# BEP31_RPM_BAR_switchedRES_2.net
KiCad netlist of a schematic drawn in EAGLE
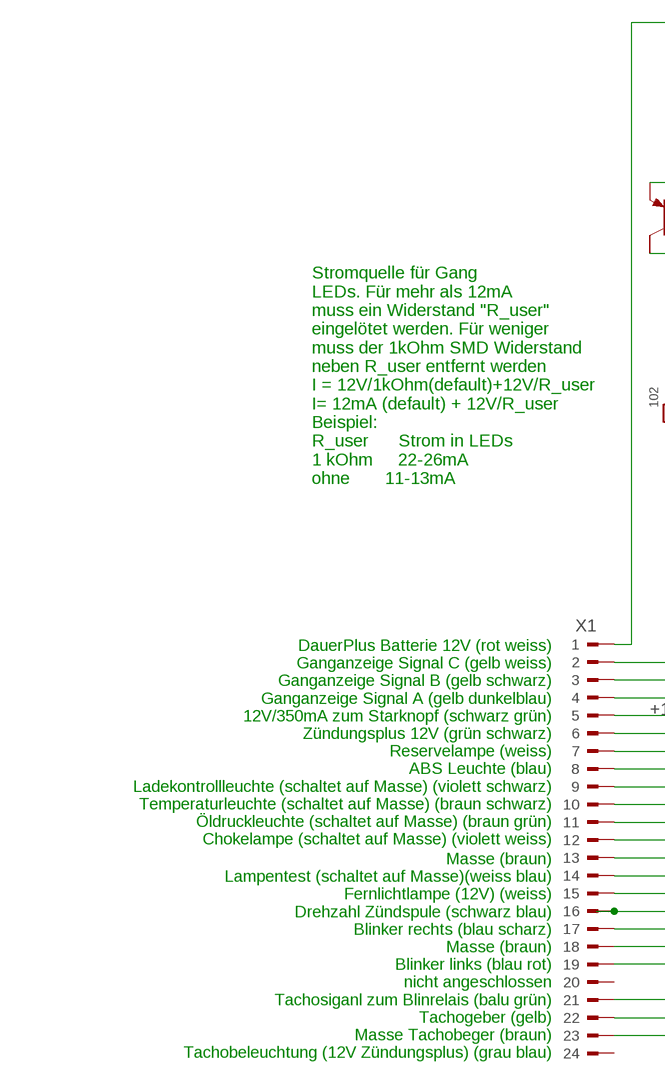
[diagram p0: schematic, sheet 1, part 1 of 2]
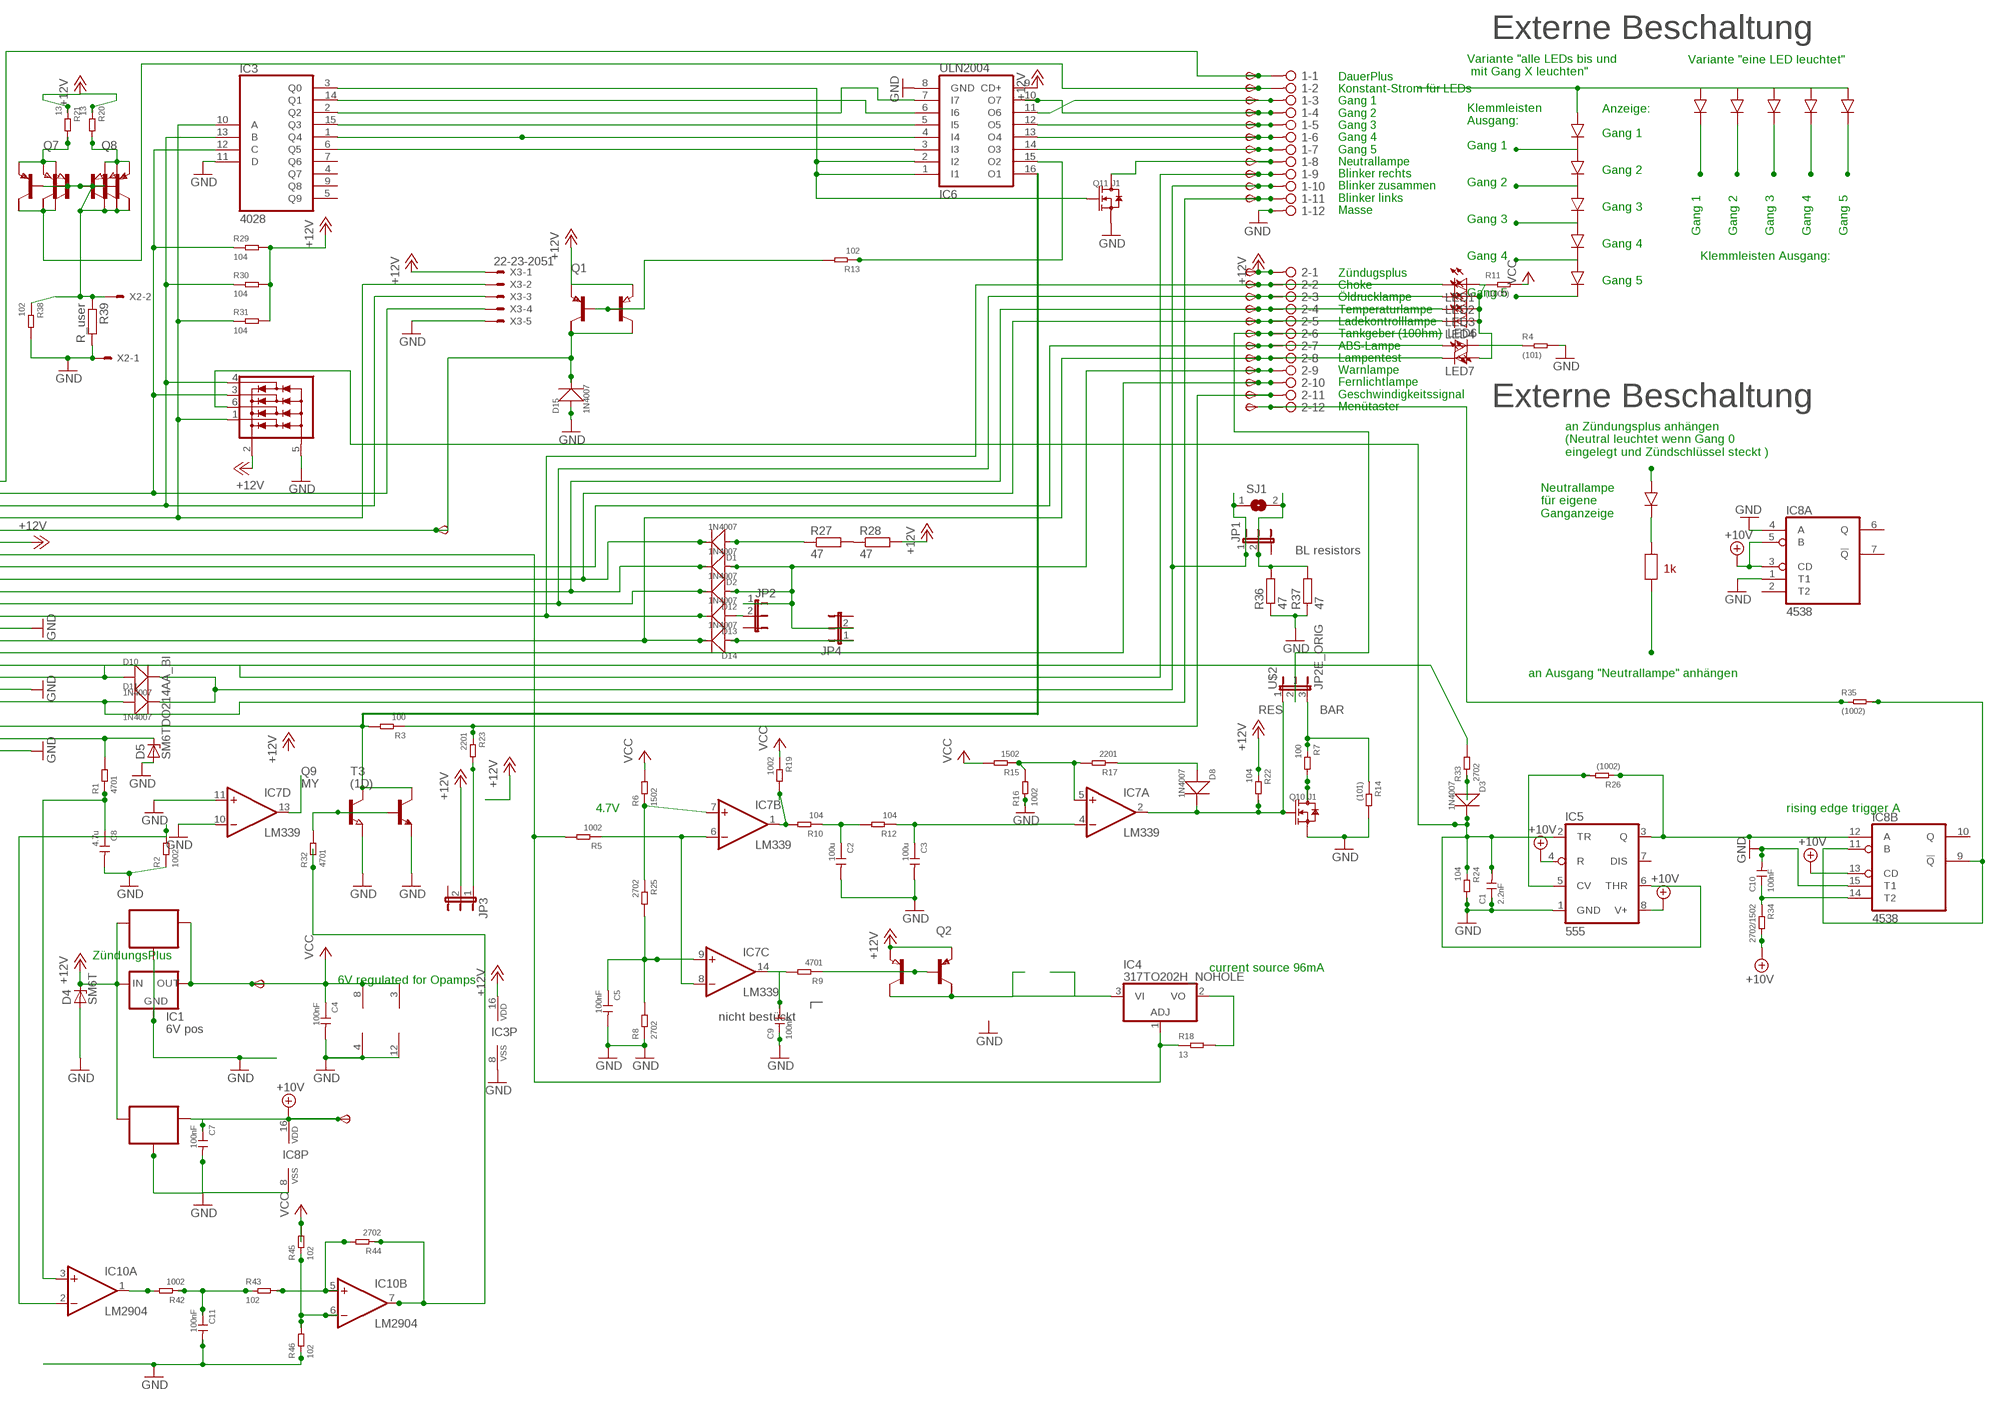
[diagram p1: schematic, sheet 1, part 2 of 2]

(export (version "E")
  (design (tool "Eeschema 10.0.6"))
  (components
    (comp (ref "1")
      (value "2081-1132")
      (footprint "eagle-import:12-PIN")
      (libsource (lib "eagle-import") (part "2081-1132"))
    )
    (comp (ref "2")
      (value "2081-1132")
      (footprint "eagle-import:12-PIN")
      (libsource (lib "eagle-import") (part "2081-1132"))
    )
    (comp (ref "6V")
      (value "TPSB2.0")
      (footprint "eagle-import:B2.0")
      (libsource (lib "eagle-import") (part "TPSB2.0"))
    )
    (comp (ref "10V")
      (value "TPSB2.0")
      (footprint "eagle-import:B2.0")
      (libsource (lib "eagle-import") (part "TPSB2.0"))
    )
    (comp (ref "C1")
      (value "2.2nF")
      (footprint "eagle-import:C0805")
      (fields (field (name "MPN") "CC0805KRX7R9BB104"))
      (libsource (lib "eagle-import") (part "CERAMIC-100NF-50V-10%-X7R(0805)"))
    )
    (comp (ref "C2")
      (value "100u")
      (footprint "eagle-import:C1206")
      (fields (field (name "MPN") "GRM31CR60J107ME39L"))
      (libsource (lib "eagle-import") (part "CERAMIC-100UF-6.3V-20%-X5R(1206)"))
    )
    (comp (ref "C3")
      (value "100u")
      (footprint "eagle-import:C1206")
      (fields (field (name "MPN") "GRM31CR60J107ME39L"))
      (libsource (lib "eagle-import") (part "CERAMIC-100UF-6.3V-20%-X5R(1206)"))
    )
    (comp (ref "C4")
      (value "100nF")
      (footprint "eagle-import:C0805")
      (fields (field (name "MPN") "CC0805KRX7R9BB104"))
      (libsource (lib "eagle-import") (part "CERAMIC-100NF-50V-10%-X7R(0805)"))
    )
    (comp (ref "C5")
      (value "100nF")
      (footprint "eagle-import:C0805")
      (fields (field (name "MPN") "CC0805KRX7R9BB104"))
      (libsource (lib "eagle-import") (part "CERAMIC-100NF-50V-10%-X7R(0805)"))
    )
    (comp (ref "C7")
      (value "100nF")
      (footprint "eagle-import:C0805")
      (fields (field (name "MPN") "CC0805KRX7R9BB104"))
      (libsource (lib "eagle-import") (part "CERAMIC-100NF-50V-10%-X7R(0805)"))
    )
    (comp (ref "C8")
      (value "4.7u")
      (footprint "eagle-import:C0805")
      (fields (field (name "MPN") "CC0805KKX5R8BB475"))
      (libsource (lib "eagle-import") (part "CERAMIC-4.7UF-25V-10%-X5R(0805)"))
    )
    (comp (ref "C9")
      (value "100nF")
      (footprint "eagle-import:C0805")
      (fields (field (name "MPN") "CC0805KRX7R9BB104"))
      (libsource (lib "eagle-import") (part "CERAMIC-100NF-50V-10%-X7R(0805)"))
    )
    (comp (ref "C10")
      (value "100nF")
      (footprint "eagle-import:C0805")
      (fields (field (name "MPN") "CC0805KRX7R9BB104"))
      (libsource (lib "eagle-import") (part "CERAMIC-100NF-50V-10%-X7R(0805)"))
    )
    (comp (ref "C11")
      (value "100nF")
      (footprint "eagle-import:C0805")
      (fields (field (name "MPN") "CC0805KRX7R9BB104"))
      (libsource (lib "eagle-import") (part "CERAMIC-100NF-50V-10%-X7R(0805)"))
    )
    (comp (ref "D1")
      (value "1N4007")
      (footprint "eagle-import:DO-214AC")
      (libsource (lib "eagle-import") (part "DIODE-GEN-PURPOSE-1KV-1A(DO-214AC)"))
    )
    (comp (ref "D2")
      (value "1N4007")
      (footprint "eagle-import:DO-214AC-1206MOUNT")
      (libsource (lib "eagle-import") (part "DIODE-GEN-PURPOSE-1KV-1A(DO-214AC)DO-214AC/1206"))
    )
    (comp (ref "D3")
      (value "1N4007")
      (footprint "eagle-import:DO-214AC")
      (libsource (lib "eagle-import") (part "DIODE-GEN-PURPOSE-1KV-1A(DO-214AC)"))
    )
    (comp (ref "D4")
      (value "SM6T")
      (footprint "eagle-import:DO214AA")
      (libsource (lib "eagle-import") (part "SM6T"))
    )
    (comp (ref "D5")
      (value "SM6TDO214AA_BI")
      (footprint "eagle-import:DO214AA_BI")
      (libsource (lib "eagle-import") (part "SM6TDO214AA_BI"))
    )
    (comp (ref "D8")
      (value "1N4007")
      (footprint "eagle-import:DO-214AC")
      (libsource (lib "eagle-import") (part "DIODE-GEN-PURPOSE-1KV-1A(DO-214AC)"))
    )
    (comp (ref "D10")
      (value "1N4007")
      (footprint "eagle-import:DO-214AC")
      (libsource (lib "eagle-import") (part "DIODE-GEN-PURPOSE-1KV-1A(DO-214AC)"))
    )
    (comp (ref "D11")
      (value "1N4007")
      (footprint "eagle-import:DO-214AC")
      (libsource (lib "eagle-import") (part "DIODE-GEN-PURPOSE-1KV-1A(DO-214AC)"))
    )
    (comp (ref "D12")
      (value "1N4007")
      (footprint "eagle-import:DO-214AC-1206MOUNT")
      (libsource (lib "eagle-import") (part "DIODE-GEN-PURPOSE-1KV-1A(DO-214AC)DO-214AC/1206"))
    )
    (comp (ref "D13")
      (value "1N4007")
      (footprint "eagle-import:DO-214AC-1206MOUNT")
      (libsource (lib "eagle-import") (part "DIODE-GEN-PURPOSE-1KV-1A(DO-214AC)DO-214AC/1206"))
    )
    (comp (ref "D14")
      (value "1N4007")
      (footprint "eagle-import:DO-214AC-1206MOUNT")
      (libsource (lib "eagle-import") (part "DIODE-GEN-PURPOSE-1KV-1A(DO-214AC)DO-214AC/1206"))
    )
    (comp (ref "D15")
      (value "1N4007")
      (footprint "eagle-import:DO-214AC")
      (libsource (lib "eagle-import") (part "DIODE-GEN-PURPOSE-1KV-1A(DO-214AC)"))
    )
    (comp (ref "IC1")
      (value "6V pos")
      (footprint "eagle-import:78LXX")
      (libsource (lib "eagle-import") (part "v-reg_78LXX"))
    )
    (comp (ref "IC2")
      (value "78LXXSOT89_ROUND")
      (footprint "eagle-import:SOT89_ROUND")
      (libsource (lib "eagle-import") (part "78LXXSOT89_ROUND"))
    )
    (comp (ref "IC3")
      (value "4028")
      (footprint "eagle-import:SO16")
      (libsource (lib "eagle-import") (part "4028D"))
    )
    (comp (ref "IC4")
      (value "317TO202H_NOHOLE")
      (footprint "eagle-import:TO220H_NOHOLE")
      (libsource (lib "eagle-import") (part "317TO202H_NOHOLE"))
    )
    (comp (ref "IC5")
      (value "555")
      (footprint "eagle-import:SO08")
      (libsource (lib "eagle-import") (part "555DNE"))
    )
    (comp (ref "IC6")
      (value "ULN2004")
      (footprint "eagle-import:SO16")
      (libsource (lib "eagle-import") (part "ULN2004AD"))
    )
    (comp (ref "IC7")
      (value "LM339")
      (footprint "eagle-import:SO14")
      (libsource (lib "eagle-import") (part "LM339D"))
    )
    (comp (ref "IC8")
      (value "4538")
      (footprint "eagle-import:SO16")
      (libsource (lib "eagle-import") (part "4538D"))
    )
    (comp (ref "IC9")
      (value "78LXXSOT89_ROUND")
      (footprint "eagle-import:SOT89_ROUND")
      (libsource (lib "eagle-import") (part "78LXXSOT89_ROUND"))
    )
    (comp (ref "IC10")
      (value "LM2904")
      (footprint "eagle-import:SO08")
      (libsource (lib "eagle-import") (part "LM358D"))
    )
    (comp (ref "JP1")
      (value "JP2EJP2_SMALLPADS")
      (footprint "eagle-import:JP2_SMALLPADS")
      (libsource (lib "eagle-import") (part "JP2EJP2_SMALLPADS"))
    )
    (comp (ref "JP2")
      (value "JP2EJP2_SMALLPADS")
      (footprint "eagle-import:JP2_SMALLPADS")
      (libsource (lib "eagle-import") (part "JP2EJP2_SMALLPADS"))
    )
    (comp (ref "JP3")
      (value "JP2EJP2_SMALLPADS")
      (footprint "eagle-import:JP2_SMALLPADS")
      (libsource (lib "eagle-import") (part "JP2EJP2_SMALLPADS"))
    )
    (comp (ref "JP4")
      (value "JP2EJP2_SMALLPADS")
      (footprint "eagle-import:JP2_SMALLPADS")
      (libsource (lib "eagle-import") (part "JP2EJP2_SMALLPADS"))
    )
    (comp (ref "LED1")
      (value "LEDLD260")
      (footprint "eagle-import:LD260")
      (libsource (lib "eagle-import") (part "LEDLD260"))
    )
    (comp (ref "LED2")
      (value "LEDLD260")
      (footprint "eagle-import:LD260")
      (libsource (lib "eagle-import") (part "LEDLD260"))
    )
    (comp (ref "LED3")
      (value "LEDLD260")
      (footprint "eagle-import:LD260")
      (libsource (lib "eagle-import") (part "LEDLD260"))
    )
    (comp (ref "LED4")
      (value "LEDLD260")
      (footprint "eagle-import:LD260")
      (libsource (lib "eagle-import") (part "LEDLD260"))
    )
    (comp (ref "LED6")
      (value "LEDLD260")
      (footprint "eagle-import:LD260")
      (libsource (lib "eagle-import") (part "LEDLD260"))
    )
    (comp (ref "LED7")
      (value "LEDLD260")
      (footprint "eagle-import:LD260")
      (libsource (lib "eagle-import") (part "LEDLD260"))
    )
    (comp (ref "Q1")
      (value "PNP-TRANSISTOR_SOT89")
      (footprint "eagle-import:SOT89")
      (libsource (lib "eagle-import") (part "PNP-TRANSISTOR_SOT89"))
    )
    (comp (ref "Q2")
      (value "PNP-TRANSISTOR_SOT89")
      (footprint "eagle-import:SOT89")
      (libsource (lib "eagle-import") (part "PNP-TRANSISTOR_SOT89"))
    )
    (comp (ref "Q3")
      (value "AH-16")
      (footprint "eagle-import:SOT223")
      (libsource (lib "eagle-import") (part "BCP53T1"))
    )
    (comp (ref "Q4")
      (value "(AH-16)")
      (footprint "eagle-import:SOT223")
      (libsource (lib "eagle-import") (part "BCP53T1"))
    )
    (comp (ref "Q5")
      (value "(AH-16)")
      (footprint "eagle-import:SOT223")
      (libsource (lib "eagle-import") (part "BCP53T1"))
    )
    (comp (ref "Q6")
      (value "(AH-16)")
      (footprint "eagle-import:SOT223")
      (libsource (lib "eagle-import") (part "BCP53T1"))
    )
    (comp (ref "Q7")
      (value "PNP-TRANSISTOR_SOT89")
      (footprint "eagle-import:SOT89")
      (libsource (lib "eagle-import") (part "PNP-TRANSISTOR_SOT89"))
    )
    (comp (ref "Q8")
      (value "PNP-TRANSISTOR_SOT89")
      (footprint "eagle-import:SOT89")
      (libsource (lib "eagle-import") (part "PNP-TRANSISTOR_SOT89"))
    )
    (comp (ref "Q9")
      (value "MY")
      (footprint "eagle-import:SOT89")
      (libsource (lib "eagle-import") (part "NPN-TRANSISTOR_SOT89"))
    )
    (comp (ref "Q10")
      (value "J1")
      (footprint "eagle-import:SOT-23")
      (fields (field (name "MPN") "BSS138W-7-F"))
      (libsource (lib "eagle-import") (part "SMD-MOSFET-N-CH-50V-200MA-BSS138W-7-F(SOT-23)"))
    )
    (comp (ref "Q11")
      (value "J1")
      (footprint "eagle-import:SOT-23")
      (fields (field (name "MPN") "BSS138W-7-F"))
      (libsource (lib "eagle-import") (part "SMD-MOSFET-N-CH-50V-200MA-BSS138W-7-F(SOT-23)"))
    )
    (comp (ref "R1")
      (value "4701")
      (footprint "eagle-import:R0805")
      (fields (field (name "MPN") "RC0805JR-074K7L"))
      (libsource (lib "eagle-import") (part "SMD-RES-4.7K-5%-1/8W(0805)"))
    )
    (comp (ref "R2")
      (value "1002")
      (footprint "eagle-import:R0805")
      (fields (field (name "MPN") "RC0805FR-0710KL"))
      (libsource (lib "eagle-import") (part "SMD-RES-10K-1%-1/8W(0805)"))
    )
    (comp (ref "R3")
      (value "100")
      (footprint "eagle-import:R0805")
      (fields (field (name "MPN") "RC0805JR-07220RL"))
      (libsource (lib "eagle-import") (part "SMD-RES-220R-5%-1/8W(0805)"))
    )
    (comp (ref "R4")
      (value "(101)")
      (footprint "eagle-import:R0805")
      (fields (field (name "MPN") "RC0805JR-07100RL"))
      (libsource (lib "eagle-import") (part "SMD-RES-100R-5%-1/8W(0805)"))
    )
    (comp (ref "R5")
      (value "1002")
      (footprint "eagle-import:R0805")
      (fields (field (name "MPN") "RC0805FR-0710KL"))
      (libsource (lib "eagle-import") (part "SMD-RES-10K-1%-1/8W(0805)"))
    )
    (comp (ref "R6")
      (value "1502")
      (footprint "eagle-import:R0805")
      (fields (field (name "MPN") "RC0805FR-0710KL"))
      (libsource (lib "eagle-import") (part "SMD-RES-10K-1%-1/8W(0805)"))
    )
    (comp (ref "R7")
      (value "100")
      (footprint "eagle-import:R0805")
      (fields (field (name "MPN") "RC0805JR-072K2L"))
      (libsource (lib "eagle-import") (part "SMD-RES-2.2K-5%-1/8W(0805)"))
    )
    (comp (ref "R8")
      (value "2702")
      (footprint "eagle-import:R0805")
      (fields (field (name "MPN") "RC0805JR-074K7L"))
      (libsource (lib "eagle-import") (part "SMD-RES-4.7K-5%-1/8W(0805)"))
    )
    (comp (ref "R9")
      (value "4701")
      (footprint "eagle-import:R0805")
      (fields (field (name "MPN") "RC0805JR-074K7L"))
      (libsource (lib "eagle-import") (part "SMD-RES-4.7K-5%-1/8W(0805)"))
    )
    (comp (ref "R10")
      (value "104")
      (footprint "eagle-import:R0805")
      (fields (field (name "MPN") "RC0805FR-0710KL"))
      (libsource (lib "eagle-import") (part "SMD-RES-10K-1%-1/8W(0805)"))
    )
    (comp (ref "R11")
      (value "(1000)")
      (footprint "eagle-import:R0805")
      (fields (field (name "MPN") "RC0805JR-07100RL"))
      (libsource (lib "eagle-import") (part "SMD-RES-100R-5%-1/8W(0805)"))
    )
    (comp (ref "R12")
      (value "104")
      (footprint "eagle-import:R0805")
      (fields (field (name "MPN") "RC0805FR-0710KL"))
      (libsource (lib "eagle-import") (part "SMD-RES-10K-1%-1/8W(0805)"))
    )
    (comp (ref "R13")
      (value "102")
      (footprint "eagle-import:R0805")
      (fields (field (name "MPN") "RC0805JR-071KL"))
      (libsource (lib "eagle-import") (part "SMD-RES-1K-5%-1/8W(0805)"))
    )
    (comp (ref "R14")
      (value "(101)")
      (footprint "eagle-import:R0805")
      (fields (field (name "MPN") "RC0805JR-072K2L"))
      (libsource (lib "eagle-import") (part "SMD-RES-2.2K-5%-1/8W(0805)"))
    )
    (comp (ref "R15")
      (value "1502")
      (footprint "eagle-import:R0805")
      (fields (field (name "MPN") "RC0805FR-0710KL"))
      (libsource (lib "eagle-import") (part "SMD-RES-10K-1%-1/8W(0805)"))
    )
    (comp (ref "R16")
      (value "1002")
      (footprint "eagle-import:R0805")
      (fields (field (name "MPN") "RC0805FR-0710KL"))
      (libsource (lib "eagle-import") (part "SMD-RES-10K-1%-1/8W(0805)"))
    )
    (comp (ref "R17")
      (value "2201")
      (footprint "eagle-import:R0805")
      (fields (field (name "MPN") "RC0805JR-072K2L"))
      (libsource (lib "eagle-import") (part "SMD-RES-2.2K-5%-1/8W(0805)"))
    )
    (comp (ref "R18")
      (value "13")
      (footprint "eagle-import:R1206")
      (fields (field (name "MPN") "RC1206JR-0713RL"))
      (libsource (lib "eagle-import") (part "SMD-RES-13R-5%-1/4W(1206)"))
    )
    (comp (ref "R19")
      (value "1002")
      (footprint "eagle-import:R0805")
      (fields (field (name "MPN") "RC0805FR-0710KL"))
      (libsource (lib "eagle-import") (part "SMD-RES-10K-1%-1/8W(0805)"))
    )
    (comp (ref "R20")
      (value "13")
      (footprint "eagle-import:R1206")
      (fields (field (name "MPN") "RC1206JR-0713RL"))
      (libsource (lib "eagle-import") (part "SMD-RES-13R-5%-1/4W(1206)"))
    )
    (comp (ref "R21")
      (value "13")
      (footprint "eagle-import:R1206")
      (fields (field (name "MPN") "RC1206JR-0713RL"))
      (libsource (lib "eagle-import") (part "SMD-RES-13R-5%-1/4W(1206)"))
    )
    (comp (ref "R22")
      (value "104")
      (footprint "eagle-import:R0805")
      (fields (field (name "MPN") "RC0805FR-0710KL"))
      (libsource (lib "eagle-import") (part "SMD-RES-10K-1%-1/8W(0805)"))
    )
    (comp (ref "R23")
      (value "2201")
      (footprint "eagle-import:R0805")
      (fields (field (name "MPN") "RC0805JR-072K2L"))
      (libsource (lib "eagle-import") (part "SMD-RES-2.2K-5%-1/8W(0805)"))
    )
    (comp (ref "R24")
      (value "104")
      (footprint "eagle-import:R0805")
      (fields (field (name "MPN") "RC0805FR-0710KL"))
      (libsource (lib "eagle-import") (part "SMD-RES-10K-1%-1/8W(0805)"))
    )
    (comp (ref "R25")
      (value "2702")
      (footprint "eagle-import:R0805")
      (fields (field (name "MPN") "RC0805JR-074K7L"))
      (libsource (lib "eagle-import") (part "SMD-RES-4.7K-5%-1/8W(0805)"))
    )
    (comp (ref "R26")
      (value "(1002)")
      (footprint "eagle-import:R0805")
      (fields (field (name "MPN") "RC0805FR-0710KL"))
      (libsource (lib "eagle-import") (part "SMD-RES-10K-1%-1/8W(0805)"))
    )
    (comp (ref "R27")
      (value "47")
      (footprint "eagle-import:V235_17_1MM")
      (libsource (lib "eagle-import") (part "R-EU_V235/17_1MM"))
    )
    (comp (ref "R28")
      (value "47")
      (footprint "eagle-import:V235_17_1MM")
      (libsource (lib "eagle-import") (part "R-EU_V235/17_1MM"))
    )
    (comp (ref "R29")
      (value "104")
      (footprint "eagle-import:R0805")
      (fields (field (name "MPN") "RC0805FR-0710KL"))
      (libsource (lib "eagle-import") (part "SMD-RES-10K-1%-1/8W(0805)"))
    )
    (comp (ref "R30")
      (value "104")
      (footprint "eagle-import:R0805")
      (fields (field (name "MPN") "RC0805FR-0710KL"))
      (libsource (lib "eagle-import") (part "SMD-RES-10K-1%-1/8W(0805)"))
    )
    (comp (ref "R31")
      (value "104")
      (footprint "eagle-import:R0805")
      (fields (field (name "MPN") "RC0805FR-0710KL"))
      (libsource (lib "eagle-import") (part "SMD-RES-10K-1%-1/8W(0805)"))
    )
    (comp (ref "R32")
      (value "4701")
      (footprint "eagle-import:R0805")
      (fields (field (name "MPN") "RC0805JR-074K7L"))
      (libsource (lib "eagle-import") (part "SMD-RES-4.7K-5%-1/8W(0805)"))
    )
    (comp (ref "R33")
      (value "2702")
      (footprint "eagle-import:R0805")
      (fields (field (name "MPN") "RC0805FR-0710KL"))
      (libsource (lib "eagle-import") (part "SMD-RES-10K-1%-1/8W(0805)"))
    )
    (comp (ref "R34")
      (value "2702/1502")
      (footprint "eagle-import:R0805")
      (fields (field (name "MPN") "RC0805JR-074K7L"))
      (libsource (lib "eagle-import") (part "SMD-RES-4.7K-5%-1/8W(0805)"))
    )
    (comp (ref "R35")
      (value "(1002)")
      (footprint "eagle-import:R0805")
      (fields (field (name "MPN") "RC0805JR-074K7L"))
      (libsource (lib "eagle-import") (part "SMD-RES-4.7K-5%-1/8W(0805)"))
    )
    (comp (ref "R36")
      (value "47")
      (footprint "eagle-import:V235_17_1MM")
      (libsource (lib "eagle-import") (part "R-EU_V235/17_1MM"))
    )
    (comp (ref "R37")
      (value "47")
      (footprint "eagle-import:V235_17_1MM")
      (libsource (lib "eagle-import") (part "R-EU_V235/17_1MM"))
    )
    (comp (ref "R38")
      (value "102")
      (footprint "eagle-import:R0805")
      (fields (field (name "MPN") "RC0805JR-071KL"))
      (libsource (lib "eagle-import") (part "SMD-RES-1K-5%-1/8W(0805)"))
    )
    (comp (ref "R39")
      (value "R_user")
      (footprint "eagle-import:R0805")
      (libsource (lib "eagle-import") (part "R-EU_R0805"))
    )
    (comp (ref "R42")
      (value "1002")
      (footprint "eagle-import:R0805")
      (fields (field (name "MPN") "RC0805FR-0710KL"))
      (libsource (lib "eagle-import") (part "SMD-RES-10K-1%-1/8W(0805)"))
    )
    (comp (ref "R43")
      (value "102")
      (footprint "eagle-import:R0805")
      (fields (field (name "MPN") "RC0805JR-071KL"))
      (libsource (lib "eagle-import") (part "SMD-RES-1K-5%-1/8W(0805)"))
    )
    (comp (ref "R44")
      (value "2702")
      (footprint "eagle-import:R0805")
      (fields (field (name "MPN") "RC0805JR-074K7L"))
      (libsource (lib "eagle-import") (part "SMD-RES-4.7K-5%-1/8W(0805)"))
    )
    (comp (ref "R45")
      (value "102")
      (footprint "eagle-import:R0805")
      (fields (field (name "MPN") "RC0805JR-071KL"))
      (libsource (lib "eagle-import") (part "SMD-RES-1K-5%-1/8W(0805)"))
    )
    (comp (ref "R46")
      (value "102")
      (footprint "eagle-import:R0805")
      (fields (field (name "MPN") "RC0805JR-071KL"))
      (libsource (lib "eagle-import") (part "SMD-RES-1K-5%-1/8W(0805)"))
    )
    (comp (ref "SJ1") (value "SJ") (footprint "eagle-import:SJ") (libsource (lib "eagle-import") (part "SJ")))
    (comp (ref "START")
      (value "TPSB2.0")
      (footprint "eagle-import:B2.0")
      (libsource (lib "eagle-import") (part "TPSB2.0"))
    )
    (comp (ref "T1")
      (value "PNP2SM8")
      (footprint "eagle-import:SM8")
      (libsource (lib "eagle-import") (part "PNP2SM8"))
    )
    (comp (ref "T3")
      (value "(1D)")
      (footprint "eagle-import:SOT23-BEC")
      (libsource (lib "eagle-import") (part "-NPN-SOT23-BECMMBTA42LT1"))
    )
    (comp (ref "TP1")
      (value "TPSB2.0")
      (footprint "eagle-import:B2.0")
      (libsource (lib "eagle-import") (part "TPSB2.0"))
    )
    (comp (ref "TP2")
      (value "TPSB2.0")
      (footprint "eagle-import:B2.0")
      (libsource (lib "eagle-import") (part "TPSB2.0"))
    )
    (comp (ref "TP3")
      (value "TPSB2.0")
      (footprint "eagle-import:B2.0")
      (libsource (lib "eagle-import") (part "TPSB2.0"))
    )
    (comp (ref "TP4")
      (value "TPSB2.0")
      (footprint "eagle-import:B2.0")
      (libsource (lib "eagle-import") (part "TPSB2.0"))
    )
    (comp (ref "TP5")
      (value "TPSB2.0")
      (footprint "eagle-import:B2.0")
      (libsource (lib "eagle-import") (part "TPSB2.0"))
    )
    (comp (ref "TP6")
      (value "TPSB2.0")
      (footprint "eagle-import:B2.0")
      (libsource (lib "eagle-import") (part "TPSB2.0"))
    )
    (comp (ref "TP7")
      (value "TPSB2.0")
      (footprint "eagle-import:B2.0")
      (libsource (lib "eagle-import") (part "TPSB2.0"))
    )
    (comp (ref "TP8")
      (value "TPSB2.0")
      (footprint "eagle-import:B2.0")
      (libsource (lib "eagle-import") (part "TPSB2.0"))
    )
    (comp (ref "TP9")
      (value "TPSB2.0")
      (footprint "eagle-import:B2.0")
      (libsource (lib "eagle-import") (part "TPSB2.0"))
    )
    (comp (ref "TP10")
      (value "TPSB2.0")
      (footprint "eagle-import:B2.0")
      (libsource (lib "eagle-import") (part "TPSB2.0"))
    )
    (comp (ref "TP11")
      (value "TPSB2.0")
      (footprint "eagle-import:B2.0")
      (libsource (lib "eagle-import") (part "TPSB2.0"))
    )
    (comp (ref "TP12")
      (value "TPSB2.0")
      (footprint "eagle-import:B2.0")
      (libsource (lib "eagle-import") (part "TPSB2.0"))
    )
    (comp (ref "TP13")
      (value "TPSB2.0")
      (footprint "eagle-import:B2.0")
      (libsource (lib "eagle-import") (part "TPSB2.0"))
    )
    (comp (ref "TP16")
      (value "TPSB2.0")
      (footprint "eagle-import:B2.0")
      (libsource (lib "eagle-import") (part "TPSB2.0"))
    )
    (comp (ref "TP17")
      (value "TPSB2.0")
      (footprint "eagle-import:B2.0")
      (libsource (lib "eagle-import") (part "TPSB2.0"))
    )
    (comp (ref "TP18")
      (value "TPSB2.0")
      (footprint "eagle-import:B2.0")
      (libsource (lib "eagle-import") (part "TPSB2.0"))
    )
    (comp (ref "TP19")
      (value "TPSB2.0")
      (footprint "eagle-import:B2.0")
      (libsource (lib "eagle-import") (part "TPSB2.0"))
    )
    (comp (ref "TP21")
      (value "TPSB2.0")
      (footprint "eagle-import:B2.0")
      (libsource (lib "eagle-import") (part "TPSB2.0"))
    )
    (comp (ref "TP22")
      (value "TPSB2.0")
      (footprint "eagle-import:B2.0")
      (libsource (lib "eagle-import") (part "TPSB2.0"))
    )
    (comp (ref "TP23")
      (value "TPSB2.0")
      (footprint "eagle-import:B2.0")
      (libsource (lib "eagle-import") (part "TPSB2.0"))
    )
    (comp (ref "TP24")
      (value "TPSB1,27")
      (footprint "eagle-import:B1,27")
      (libsource (lib "eagle-import") (part "TPSB1,27"))
    )
    (comp (ref "TP25")
      (value "TPSB2.0")
      (footprint "eagle-import:B2.0")
      (libsource (lib "eagle-import") (part "TPSB2.0"))
    )
    (comp (ref "TP26")
      (value "TPSB2.0")
      (footprint "eagle-import:B2.0")
      (libsource (lib "eagle-import") (part "TPSB2.0"))
    )
    (comp (ref "U$2")
      (value "JP2E_ORIG")
      (footprint "eagle-import:JP2_ORIG_SMALLPADS")
      (libsource (lib "eagle-import") (part "JP2E_ORIG"))
    )
    (comp (ref "U$3")
      (value "NUP4304SOT457_R")
      (footprint "eagle-import:SOT457R_PHILIPS")
      (libsource (lib "eagle-import") (part "NUP4304SOT457_R"))
    )
    (comp (ref "X1")
      (value "CON_BMWV2")
      (footprint "eagle-import:24-PIN_V2")
      (libsource (lib "eagle-import") (part "CON_BMWV2"))
    )
    (comp (ref "X2")
      (value "22-23-2021")
      (footprint "eagle-import:22-23-2021")
      (fields (field (name "MF") "MOLEX"))
      (libsource (lib "eagle-import") (part "22-23-2021"))
    )
    (comp (ref "X3")
      (value "22-23-2051")
      (footprint "eagle-import:22-23-2051")
      (fields (field (name "MF") "MOLEX"))
      (libsource (lib "eagle-import") (part "22-23-2051"))
    )
  )
  (nets
    (net (code "1") (name "+10V") (class "Default")
      (node (ref "10V") (pin "TP") (pinfunction "PP_TP") (pintype "input"))
      (node (ref "C7") (pin "1") (pinfunction "1_1") (pintype "passive"))
      (node (ref "IC5") (pin "4") (pinfunction "R_4") (pintype "input"))
      (node (ref "IC5") (pin "8") (pinfunction "V+_8") (pintype "power_in"))
      (node (ref "IC8") (pin "13") (pinfunction "CD_13") (pintype "input"))
      (node (ref "IC8") (pin "16") (pinfunction "VDD_16") (pintype "power_in"))
      (node (ref "IC8") (pin "3") (pinfunction "CD_3") (pintype "input"))
      (node (ref "IC8") (pin "5") (pinfunction "B_5") (pintype "input"))
      (node (ref "IC9") (pin "1") (pinfunction "OUT_1") (pintype "passive"))
      (node (ref "R34") (pin "2") (pinfunction "2_2") (pintype "passive"))
    )
    (net (code "2") (name "+12V") (class "Default")
      (node (ref "2") (pin "1") (pinfunction "KL_1") (pintype "passive"))
      (node (ref "D4") (pin "C") (pinfunction "C_C") (pintype "passive"))
      (node (ref "IC1") (pin "IN") (pinfunction "IN_IN") (pintype "input"))
      (node (ref "IC2") (pin "3") (pinfunction "IN_3") (pintype "input"))
      (node (ref "IC3") (pin "16") (pinfunction "VDD_16") (pintype "power_in"))
      (node (ref "IC6") (pin "9") (pinfunction "CD+_9") (pintype "passive"))
      (node (ref "IC9") (pin "3") (pinfunction "IN_3") (pintype "input"))
      (node (ref "JP3") (pin "2") (pinfunction "2_2") (pintype "passive"))
      (node (ref "Q1") (pin "3") (pinfunction "E_3") (pintype "passive"))
      (node (ref "Q2") (pin "3") (pinfunction "E_3") (pintype "passive"))
      (node (ref "Q3") (pin "3") (pinfunction "E_3") (pintype "passive"))
      (node (ref "Q4") (pin "3") (pinfunction "E_3") (pintype "passive"))
      (node (ref "R20") (pin "1") (pinfunction "1_1") (pintype "passive"))
      (node (ref "R21") (pin "1") (pinfunction "1_1") (pintype "passive"))
      (node (ref "R22") (pin "1") (pinfunction "1_1") (pintype "passive"))
      (node (ref "R28") (pin "2") (pinfunction "2_2") (pintype "passive"))
      (node (ref "R29") (pin "2") (pinfunction "2_2") (pintype "passive"))
      (node (ref "R30") (pin "2") (pinfunction "2_2") (pintype "passive"))
      (node (ref "R31") (pin "2") (pinfunction "2_2") (pintype "passive"))
      (node (ref "TP12") (pin "TP") (pinfunction "PP_TP") (pintype "input"))
      (node (ref "U$3") (pin "2") (pinfunction "V+_2") (pintype "passive"))
      (node (ref "X1") (pin "6") (pinfunction "6_6") (pintype "passive"))
      (node (ref "X3") (pin "1") (pinfunction "S_1") (pintype "passive"))
    )
    (net (code "3") (name "GND") (class "Default")
      (node (ref "1") (pin "12") (pinfunction "KL_12") (pintype "passive"))
      (node (ref "C1") (pin "1") (pinfunction "1_1") (pintype "passive"))
      (node (ref "C10") (pin "2") (pinfunction "2_2") (pintype "passive"))
      (node (ref "C11") (pin "2") (pinfunction "2_2") (pintype "passive"))
      (node (ref "C2") (pin "2") (pinfunction "2_2") (pintype "passive"))
      (node (ref "C3") (pin "2") (pinfunction "2_2") (pintype "passive"))
      (node (ref "C4") (pin "2") (pinfunction "2_2") (pintype "passive"))
      (node (ref "C5") (pin "2") (pinfunction "2_2") (pintype "passive"))
      (node (ref "C7") (pin "2") (pinfunction "2_2") (pintype "passive"))
      (node (ref "C8") (pin "2") (pinfunction "2_2") (pintype "passive"))
      (node (ref "C9") (pin "1") (pinfunction "1_1") (pintype "passive"))
      (node (ref "D15") (pin "1") (pinfunction "+_1") (pintype "passive"))
      (node (ref "D4") (pin "A") (pinfunction "A_A") (pintype "passive"))
      (node (ref "D5") (pin "A") (pinfunction "A_A") (pintype "passive"))
      (node (ref "IC1") (pin "GND") (pinfunction "GND_GND") (pintype "input"))
      (node (ref "IC10") (pin "4") (pinfunction "V-_4") (pintype "power_in"))
      (node (ref "IC2") (pin "2") (pinfunction "GND_2") (pintype "input"))
      (node (ref "IC2") (pin "2@1") (pinfunction "GND_2@1") (pintype "input"))
      (node (ref "IC3") (pin "11") (pinfunction "D_11") (pintype "input"))
      (node (ref "IC3") (pin "8") (pinfunction "VSS_8") (pintype "power_in"))
      (node (ref "IC5") (pin "1") (pinfunction "GND_1") (pintype "power_in"))
      (node (ref "IC6") (pin "8") (pinfunction "GND_8") (pintype "power_in"))
      (node (ref "IC7") (pin "10") (pinfunction "-IN_10") (pintype "input"))
      (node (ref "IC7") (pin "11") (pinfunction "+IN_11") (pintype "input"))
      (node (ref "IC7") (pin "12") (pinfunction "GND_12") (pintype "power_in"))
      (node (ref "IC8") (pin "1") (pinfunction "T1_1") (pintype "input"))
      (node (ref "IC8") (pin "15") (pinfunction "T1_15") (pintype "input"))
      (node (ref "IC8") (pin "4") (pinfunction "A_4") (pintype "input"))
      (node (ref "IC8") (pin "8") (pinfunction "VSS_8") (pintype "power_in"))
      (node (ref "IC9") (pin "2") (pinfunction "GND_2") (pintype "input"))
      (node (ref "IC9") (pin "2@1") (pinfunction "GND_2@1") (pintype "input"))
      (node (ref "Q10") (pin "2") (pinfunction "S_2") (pintype "passive"))
      (node (ref "Q11") (pin "2") (pinfunction "S_2") (pintype "passive"))
      (node (ref "Q9") (pin "3") (pinfunction "E_3") (pintype "passive"))
      (node (ref "R14") (pin "2") (pinfunction "2_2") (pintype "passive"))
      (node (ref "R16") (pin "1") (pinfunction "1_1") (pintype "passive"))
      (node (ref "R2") (pin "1") (pinfunction "1_1") (pintype "passive"))
      (node (ref "R24") (pin "2") (pinfunction "2_2") (pintype "passive"))
      (node (ref "R36") (pin "1") (pinfunction "1_1") (pintype "passive"))
      (node (ref "R37") (pin "1") (pinfunction "1_1") (pintype "passive"))
      (node (ref "R38") (pin "2") (pinfunction "2_2") (pintype "passive"))
      (node (ref "R39") (pin "2") (pinfunction "2_2") (pintype "passive"))
      (node (ref "R4") (pin "2") (pinfunction "2_2") (pintype "passive"))
      (node (ref "R46") (pin "1") (pinfunction "1_1") (pintype "passive"))
      (node (ref "R8") (pin "1") (pinfunction "1_1") (pintype "passive"))
      (node (ref "T3") (pin "E") (pinfunction "E_E") (pintype "passive"))
      (node (ref "U$3") (pin "5") (pinfunction "V-_5") (pintype "passive"))
      (node (ref "X1") (pin "13") (pinfunction "13_13") (pintype "passive"))
      (node (ref "X1") (pin "18") (pinfunction "18_18") (pintype "passive"))
      (node (ref "X1") (pin "23") (pinfunction "23_23") (pintype "passive"))
      (node (ref "X2") (pin "1") (pinfunction "S_1") (pintype "passive"))
      (node (ref "X3") (pin "5") (pinfunction "S_5") (pintype "passive"))
    )
    (net (code "4") (name "Net-(1A-KL)") (class "Default")
      (node (ref "1") (pin "1") (pinfunction "KL_1") (pintype "passive"))
      (node (ref "TP1") (pin "TP") (pinfunction "PP_TP") (pintype "input"))
      (node (ref "X1") (pin "1") (pinfunction "1_1") (pintype "passive"))
    )
    (net (code "5") (name "Net-(1B-KL)") (class "Default")
      (node (ref "1") (pin "10") (pinfunction "KL_10") (pintype "passive"))
      (node (ref "D10") (pin "2") (pinfunction "-_2") (pintype "passive"))
      (node (ref "D11") (pin "2") (pinfunction "-_2") (pintype "passive"))
      (node (ref "JP1") (pin "1") (pinfunction "1_1") (pintype "passive"))
      (node (ref "SJ1") (pin "1") (pinfunction "1_1") (pintype "passive"))
      (node (ref "TP10") (pin "TP") (pinfunction "PP_TP") (pintype "input"))
    )
    (net (code "6") (name "Net-(1C-KL)") (class "Default")
      (node (ref "1") (pin "11") (pinfunction "KL_11") (pintype "passive"))
      (node (ref "D11") (pin "1") (pinfunction "+_1") (pintype "passive"))
      (node (ref "TP11") (pin "TP") (pinfunction "PP_TP") (pintype "input"))
      (node (ref "X1") (pin "19") (pinfunction "19_19") (pintype "passive"))
    )
    (net (code "7") (name "Net-(1E-KL)") (class "Default")
      (node (ref "1") (pin "2") (pinfunction "KL_2") (pintype "passive"))
      (node (ref "Q5") (pin "2") (pinfunction "C_2") (pintype "passive"))
      (node (ref "Q8") (pin "2") (pinfunction "C_2") (pintype "passive"))
      (node (ref "T1") (pin "8") (pinfunction "C1_8") (pintype "passive"))
      (node (ref "TP2") (pin "TP") (pinfunction "PP_TP") (pintype "input"))
    )
    (net (code "8") (name "Net-(1F-KL)") (class "Default")
      (node (ref "1") (pin "3") (pinfunction "KL_3") (pintype "passive"))
      (node (ref "IC6") (pin "11") (pinfunction "O6_11") (pintype "open_collector"))
      (node (ref "TP3") (pin "TP") (pinfunction "PP_TP") (pintype "input"))
    )
    (net (code "9") (name "Net-(1G-KL)") (class "Default")
      (node (ref "1") (pin "4") (pinfunction "KL_4") (pintype "passive"))
      (node (ref "IC6") (pin "10") (pinfunction "O7_10") (pintype "open_collector"))
      (node (ref "TP4") (pin "TP") (pinfunction "PP_TP") (pintype "input"))
    )
    (net (code "10") (name "Net-(1H-KL)") (class "Default")
      (node (ref "1") (pin "5") (pinfunction "KL_5") (pintype "passive"))
      (node (ref "IC6") (pin "12") (pinfunction "O5_12") (pintype "open_collector"))
      (node (ref "TP5") (pin "TP") (pinfunction "PP_TP") (pintype "input"))
    )
    (net (code "11") (name "Net-(1I-KL)") (class "Default")
      (node (ref "1") (pin "6") (pinfunction "KL_6") (pintype "passive"))
      (node (ref "IC6") (pin "13") (pinfunction "O4_13") (pintype "open_collector"))
      (node (ref "TP6") (pin "TP") (pinfunction "PP_TP") (pintype "input"))
    )
    (net (code "12") (name "Net-(1J-KL)") (class "Default")
      (node (ref "1") (pin "7") (pinfunction "KL_7") (pintype "passive"))
      (node (ref "IC6") (pin "14") (pinfunction "O3_14") (pintype "open_collector"))
      (node (ref "TP7") (pin "TP") (pinfunction "PP_TP") (pintype "input"))
    )
    (net (code "13") (name "Net-(1K-KL)") (class "Default")
      (node (ref "1") (pin "8") (pinfunction "KL_8") (pintype "passive"))
      (node (ref "Q11") (pin "3") (pinfunction "D_3") (pintype "passive"))
      (node (ref "TP8") (pin "TP") (pinfunction "PP_TP") (pintype "input"))
    )
    (net (code "14") (name "Net-(1L-KL)") (class "Default")
      (node (ref "1") (pin "9") (pinfunction "KL_9") (pintype "passive"))
      (node (ref "D10") (pin "1") (pinfunction "+_1") (pintype "passive"))
      (node (ref "TP9") (pin "TP") (pinfunction "PP_TP") (pintype "input"))
      (node (ref "X1") (pin "17") (pinfunction "17_17") (pintype "passive"))
    )
    (net (code "15") (name "Net-(2B-KL)") (class "Default")
      (node (ref "2") (pin "10") (pinfunction "KL_10") (pintype "passive"))
      (node (ref "TP25") (pin "TP") (pinfunction "PP_TP") (pintype "input"))
      (node (ref "X1") (pin "15") (pinfunction "15_15") (pintype "passive"))
    )
    (net (code "16") (name "Net-(2C-KL)") (class "Default")
      (node (ref "2") (pin "11") (pinfunction "KL_11") (pintype "passive"))
      (node (ref "R23") (pin "1") (pinfunction "1_1") (pintype "passive"))
      (node (ref "R3") (pin "1") (pinfunction "1_1") (pintype "passive"))
      (node (ref "TP26") (pin "TP") (pinfunction "PP_TP") (pintype "input"))
    )
    (net (code "17") (name "Net-(2D-KL)") (class "Default")
      (node (ref "2") (pin "12") (pinfunction "KL_12") (pintype "passive"))
      (node (ref "R35") (pin "1") (pinfunction "1_1") (pintype "passive"))
      (node (ref "TP13") (pin "TP") (pinfunction "PP_TP") (pintype "input"))
    )
    (net (code "18") (name "Net-(2E-KL)") (class "Default")
      (node (ref "2") (pin "2") (pinfunction "KL_2") (pintype "passive"))
      (node (ref "D13") (pin "2") (pinfunction "-_2") (pintype "passive"))
      (node (ref "LED1") (pin "K") (pinfunction "C_K") (pintype "passive"))
      (node (ref "TP16") (pin "TP") (pinfunction "PP_TP") (pintype "input"))
      (node (ref "X1") (pin "12") (pinfunction "12_12") (pintype "passive"))
    )
    (net (code "19") (name "Net-(2F-KL)") (class "Default")
      (node (ref "2") (pin "3") (pinfunction "KL_3") (pintype "passive"))
      (node (ref "D12") (pin "2") (pinfunction "-_2") (pintype "passive"))
      (node (ref "LED2") (pin "K") (pinfunction "C_K") (pintype "passive"))
      (node (ref "TP17") (pin "TP") (pinfunction "PP_TP") (pintype "input"))
      (node (ref "X1") (pin "11") (pinfunction "11_11") (pintype "passive"))
    )
    (net (code "20") (name "Net-(2G-KL)") (class "Default")
      (node (ref "2") (pin "4") (pinfunction "KL_4") (pintype "passive"))
      (node (ref "D2") (pin "2") (pinfunction "-_2") (pintype "passive"))
      (node (ref "LED3") (pin "K") (pinfunction "C_K") (pintype "passive"))
      (node (ref "TP18") (pin "TP") (pinfunction "PP_TP") (pintype "input"))
      (node (ref "X1") (pin "10") (pinfunction "10_10") (pintype "passive"))
    )
    (net (code "21") (name "Net-(2H-KL)") (class "Default")
      (node (ref "2") (pin "5") (pinfunction "KL_5") (pintype "passive"))
      (node (ref "D1") (pin "2") (pinfunction "-_2") (pintype "passive"))
      (node (ref "LED4") (pin "K") (pinfunction "C_K") (pintype "passive"))
      (node (ref "TP19") (pin "TP") (pinfunction "PP_TP") (pintype "input"))
      (node (ref "X1") (pin "9") (pinfunction "9_9") (pintype "passive"))
    )
    (net (code "22") (name "Net-(2I-KL)") (class "Default")
      (node (ref "2") (pin "6") (pinfunction "KL_6") (pintype "passive"))
      (node (ref "TP21") (pin "TP") (pinfunction "PP_TP") (pintype "input"))
      (node (ref "U$2") (pin "2") (pinfunction "2_2") (pintype "passive"))
    )
    (net (code "23") (name "Net-(2J-KL)") (class "Default")
      (node (ref "2") (pin "7") (pinfunction "KL_7") (pintype "passive"))
      (node (ref "LED6") (pin "A") (pinfunction "A_A") (pintype "passive"))
      (node (ref "TP22") (pin "TP") (pinfunction "PP_TP") (pintype "input"))
      (node (ref "X1") (pin "8") (pinfunction "8_8") (pintype "passive"))
    )
    (net (code "24") (name "Net-(2K-KL)") (class "Default")
      (node (ref "2") (pin "8") (pinfunction "KL_8") (pintype "passive"))
      (node (ref "D14") (pin "2") (pinfunction "-_2") (pintype "passive"))
      (node (ref "LED7") (pin "K") (pinfunction "C_K") (pintype "passive"))
      (node (ref "TP23") (pin "TP") (pinfunction "PP_TP") (pintype "input"))
      (node (ref "X1") (pin "14") (pinfunction "14_14") (pintype "passive"))
    )
    (net (code "25") (name "Net-(2L-KL)") (class "Default")
      (node (ref "2") (pin "9") (pinfunction "KL_9") (pintype "passive"))
      (node (ref "D12") (pin "1") (pinfunction "+_1") (pintype "passive"))
      (node (ref "D2") (pin "1") (pinfunction "+_1") (pintype "passive"))
      (node (ref "JP2") (pin "1") (pinfunction "1_1") (pintype "passive"))
      (node (ref "JP4") (pin "2") (pinfunction "2_2") (pintype "passive"))
      (node (ref "TP24") (pin "TP") (pinfunction "PP_TP") (pintype "input"))
    )
    (net (code "26") (name "Net-(C2-Pad1)") (class "Default")
      (node (ref "C2") (pin "1") (pinfunction "1_1") (pintype "passive"))
      (node (ref "R10") (pin "1") (pinfunction "1_1") (pintype "passive"))
      (node (ref "R12") (pin "2") (pinfunction "2_2") (pintype "passive"))
    )
    (net (code "27") (name "Net-(C11-Pad1)") (class "Default")
      (node (ref "C11") (pin "1") (pinfunction "1_1") (pintype "passive"))
      (node (ref "R42") (pin "1") (pinfunction "1_1") (pintype "passive"))
      (node (ref "R43") (pin "1") (pinfunction "1_1") (pintype "passive"))
    )
    (net (code "28") (name "Net-(D1-+)") (class "Default")
      (node (ref "D1") (pin "1") (pinfunction "+_1") (pintype "passive"))
      (node (ref "R27") (pin "1") (pinfunction "1_1") (pintype "passive"))
    )
    (net (code "29") (name "Net-(D3-+)") (class "Default")
      (node (ref "D3") (pin "1") (pinfunction "+_1") (pintype "passive"))
      (node (ref "R33") (pin "1") (pinfunction "1_1") (pintype "passive"))
    )
    (net (code "30") (name "Net-(D3--)") (class "Default")
      (node (ref "C1") (pin "2") (pinfunction "2_2") (pintype "passive"))
      (node (ref "D3") (pin "2") (pinfunction "-_2") (pintype "passive"))
      (node (ref "IC5") (pin "2") (pinfunction "TR_2") (pintype "input"))
      (node (ref "IC5") (pin "6") (pinfunction "THR_6") (pintype "input"))
      (node (ref "R24") (pin "1") (pinfunction "1_1") (pintype "passive"))
      (node (ref "U$3") (pin "6") (pinfunction "D2_6") (pintype "passive"))
    )
    (net (code "31") (name "Net-(D5-PadC)") (class "Default")
      (node (ref "D5") (pin "C") (pinfunction "C_C") (pintype "passive"))
      (node (ref "R1") (pin "2") (pinfunction "2_2") (pintype "passive"))
      (node (ref "X1") (pin "22") (pinfunction "22_22") (pintype "passive"))
    )
    (net (code "32") (name "Net-(D8-+)") (class "Default")
      (node (ref "D8") (pin "1") (pinfunction "+_1") (pintype "passive"))
      (node (ref "R17") (pin "1") (pinfunction "1_1") (pintype "passive"))
    )
    (net (code "33") (name "Net-(D8--)") (class "Default")
      (node (ref "D8") (pin "2") (pinfunction "-_2") (pintype "passive"))
      (node (ref "IC7") (pin "2") (pinfunction "OUT_2") (pintype "open_collector"))
      (node (ref "Q10") (pin "1") (pinfunction "G_1") (pintype "passive"))
      (node (ref "R22") (pin "2") (pinfunction "2_2") (pintype "passive"))
      (node (ref "U$2") (pin "1") (pinfunction "1_1") (pintype "passive"))
    )
    (net (code "34") (name "Net-(D13-+)") (class "Default")
      (node (ref "D13") (pin "1") (pinfunction "+_1") (pintype "passive"))
      (node (ref "JP2") (pin "2") (pinfunction "2_2") (pintype "passive"))
    )
    (net (code "35") (name "Net-(D14-+)") (class "Default")
      (node (ref "D14") (pin "1") (pinfunction "+_1") (pintype "passive"))
      (node (ref "JP4") (pin "1") (pinfunction "1_1") (pintype "passive"))
    )
    (net (code "36") (name "Net-(D15--)") (class "Default")
      (node (ref "D15") (pin "2") (pinfunction "-_2") (pintype "passive"))
      (node (ref "Q1") (pin "2") (pinfunction "C_2") (pintype "passive"))
      (node (ref "Q3") (pin "2") (pinfunction "C_2") (pintype "passive"))
      (node (ref "START") (pin "TP") (pinfunction "PP_TP") (pintype "input"))
      (node (ref "X1") (pin "5") (pinfunction "5_5") (pintype "passive"))
    )
    (net (code "37") (name "Net-(IC3A-A)") (class "Default")
      (node (ref "IC3") (pin "10") (pinfunction "A_10") (pintype "input"))
      (node (ref "R31") (pin "1") (pinfunction "1_1") (pintype "passive"))
      (node (ref "U$3") (pin "1") (pinfunction "D1_1") (pintype "passive"))
      (node (ref "X1") (pin "4") (pinfunction "4_4") (pintype "passive"))
      (node (ref "X3") (pin "2") (pinfunction "S_2") (pintype "passive"))
    )
    (net (code "38") (name "Net-(IC3A-B)") (class "Default")
      (node (ref "IC3") (pin "13") (pinfunction "B_13") (pintype "input"))
      (node (ref "R30") (pin "1") (pinfunction "1_1") (pintype "passive"))
      (node (ref "U$3") (pin "4") (pinfunction "D4_4") (pintype "passive"))
      (node (ref "X1") (pin "3") (pinfunction "3_3") (pintype "passive"))
      (node (ref "X3") (pin "3") (pinfunction "S_3") (pintype "passive"))
    )
    (net (code "39") (name "Net-(IC3A-C)") (class "Default")
      (node (ref "IC3") (pin "12") (pinfunction "C_12") (pintype "input"))
      (node (ref "R29") (pin "1") (pinfunction "1_1") (pintype "passive"))
      (node (ref "U$3") (pin "3") (pinfunction "D3_3") (pintype "passive"))
      (node (ref "X1") (pin "2") (pinfunction "2_2") (pintype "passive"))
      (node (ref "X3") (pin "4") (pinfunction "S_4") (pintype "passive"))
    )
    (net (code "40") (name "Net-(IC3A-Q0)") (class "Default")
      (node (ref "IC3") (pin "3") (pinfunction "Q0_3") (pintype "output"))
      (node (ref "IC6") (pin "1") (pinfunction "I1_1") (pintype "input"))
      (node (ref "IC6") (pin "2") (pinfunction "I2_2") (pintype "input"))
      (node (ref "Q11") (pin "1") (pinfunction "G_1") (pintype "passive"))
    )
    (net (code "41") (name "Net-(IC3A-Q1)") (class "Default")
      (node (ref "IC3") (pin "14") (pinfunction "Q1_14") (pintype "output"))
      (node (ref "IC6") (pin "6") (pinfunction "I6_6") (pintype "input"))
    )
    (net (code "42") (name "Net-(IC3A-Q2)") (class "Default")
      (node (ref "IC3") (pin "2") (pinfunction "Q2_2") (pintype "output"))
      (node (ref "IC6") (pin "7") (pinfunction "I7_7") (pintype "input"))
    )
    (net (code "43") (name "Net-(IC3A-Q3)") (class "Default")
      (node (ref "IC3") (pin "15") (pinfunction "Q3_15") (pintype "output"))
      (node (ref "IC6") (pin "5") (pinfunction "I5_5") (pintype "input"))
    )
    (net (code "44") (name "Net-(IC3A-Q4)") (class "Default")
      (node (ref "IC3") (pin "1") (pinfunction "Q4_1") (pintype "output"))
      (node (ref "IC6") (pin "4") (pinfunction "I4_4") (pintype "input"))
    )
    (net (code "45") (name "Net-(IC3A-Q5)") (class "Default")
      (node (ref "IC3") (pin "6") (pinfunction "Q5_6") (pintype "output"))
      (node (ref "IC6") (pin "3") (pinfunction "I3_3") (pintype "input"))
    )
    (net (code "46") (name "Net-(IC4-ADJ)") (class "Default")
      (node (ref "IC4") (pin "1") (pinfunction "ADJ_1") (pintype "input"))
      (node (ref "R18") (pin "1") (pinfunction "1_1") (pintype "passive"))
      (node (ref "R5") (pin "2") (pinfunction "2_2") (pintype "passive"))
      (node (ref "X1") (pin "7") (pinfunction "7_7") (pintype "passive"))
    )
    (net (code "47") (name "Net-(IC4-VI)") (class "Default")
      (node (ref "IC4") (pin "3") (pinfunction "VI_3") (pintype "input"))
      (node (ref "Q2") (pin "2") (pinfunction "C_2") (pintype "passive"))
      (node (ref "Q4") (pin "2") (pinfunction "C_2") (pintype "passive"))
    )
    (net (code "48") (name "Net-(IC4-VO)") (class "Default")
      (node (ref "IC4") (pin "2") (pinfunction "VO_2") (pintype "passive"))
      (node (ref "R18") (pin "2") (pinfunction "2_2") (pintype "passive"))
    )
    (net (code "49") (name "Net-(IC5-CV)") (class "Default")
      (node (ref "IC5") (pin "5") (pinfunction "CV_5") (pintype "input"))
      (node (ref "R26") (pin "2") (pinfunction "2_2") (pintype "passive"))
    )
    (net (code "50") (name "Net-(IC5-Q)") (class "Default")
      (node (ref "IC5") (pin "3") (pinfunction "Q_3") (pintype "output"))
      (node (ref "IC8") (pin "12") (pinfunction "A_12") (pintype "input"))
      (node (ref "R26") (pin "1") (pinfunction "1_1") (pintype "passive"))
    )
    (net (code "51") (name "Net-(IC6-O1)") (class "Default")
      (node (ref "IC6") (pin "16") (pinfunction "O1_16") (pintype "open_collector"))
      (node (ref "Q9") (pin "2") (pinfunction "C_2") (pintype "passive"))
      (node (ref "R3") (pin "2") (pinfunction "2_2") (pintype "passive"))
      (node (ref "T3") (pin "C") (pinfunction "C_C") (pintype "passive"))
      (node (ref "X1") (pin "21") (pinfunction "21_21") (pintype "passive"))
    )
    (net (code "52") (name "Net-(IC6-O2)") (class "Default")
      (node (ref "IC6") (pin "15") (pinfunction "O2_15") (pintype "open_collector"))
      (node (ref "R13") (pin "1") (pinfunction "1_1") (pintype "passive"))
    )
    (net (code "53") (name "Net-(IC7A-+IN)") (class "Default")
      (node (ref "IC7") (pin "5") (pinfunction "+IN_5") (pintype "input"))
      (node (ref "R15") (pin "1") (pinfunction "1_1") (pintype "passive"))
      (node (ref "R16") (pin "2") (pinfunction "2_2") (pintype "passive"))
      (node (ref "R17") (pin "2") (pinfunction "2_2") (pintype "passive"))
    )
    (net (code "54") (name "Net-(IC7A--IN)") (class "Default")
      (node (ref "C3") (pin "1") (pinfunction "1_1") (pintype "passive"))
      (node (ref "IC7") (pin "4") (pinfunction "-IN_4") (pintype "input"))
      (node (ref "R12") (pin "1") (pinfunction "1_1") (pintype "passive"))
    )
    (net (code "55") (name "Net-(IC7B-+IN)") (class "Default")
      (node (ref "IC7") (pin "7") (pinfunction "+IN_7") (pintype "input"))
      (node (ref "R25") (pin "1") (pinfunction "1_1") (pintype "passive"))
      (node (ref "R6") (pin "1") (pinfunction "1_1") (pintype "passive"))
    )
    (net (code "56") (name "Net-(IC7B--IN)") (class "Default")
      (node (ref "IC7") (pin "6") (pinfunction "-IN_6") (pintype "input"))
      (node (ref "IC7") (pin "8") (pinfunction "-IN_8") (pintype "input"))
      (node (ref "R5") (pin "1") (pinfunction "1_1") (pintype "passive"))
    )
    (net (code "57") (name "Net-(IC7B-OUT)") (class "Default")
      (node (ref "IC7") (pin "1") (pinfunction "OUT_1") (pintype "open_collector"))
      (node (ref "R10") (pin "2") (pinfunction "2_2") (pintype "passive"))
      (node (ref "R19") (pin "2") (pinfunction "2_2") (pintype "passive"))
    )
    (net (code "58") (name "Net-(IC7C-+IN)") (class "Default")
      (node (ref "C5") (pin "1") (pinfunction "1_1") (pintype "passive"))
      (node (ref "IC7") (pin "9") (pinfunction "+IN_9") (pintype "input"))
      (node (ref "R25") (pin "2") (pinfunction "2_2") (pintype "passive"))
      (node (ref "R8") (pin "2") (pinfunction "2_2") (pintype "passive"))
    )
    (net (code "59") (name "Net-(IC7C-OUT)") (class "Default")
      (node (ref "C9") (pin "2") (pinfunction "2_2") (pintype "passive"))
      (node (ref "IC7") (pin "14") (pinfunction "OUT_14") (pintype "open_collector"))
      (node (ref "R9") (pin "2") (pinfunction "2_2") (pintype "passive"))
    )
    (net (code "60") (name "Net-(IC8B-B)") (class "Default")
      (node (ref "IC8") (pin "11") (pinfunction "B_11") (pintype "input"))
      (node (ref "IC8") (pin "9") (pinfunction "~{Q}_9") (pintype "output"))
      (node (ref "R35") (pin "2") (pinfunction "2_2") (pintype "passive"))
    )
    (net (code "61") (name "Net-(IC8B-T2)") (class "Default")
      (node (ref "C10") (pin "1") (pinfunction "1_1") (pintype "passive"))
      (node (ref "IC8") (pin "14") (pinfunction "T2_14") (pintype "input"))
      (node (ref "R34") (pin "1") (pinfunction "1_1") (pintype "passive"))
    )
    (net (code "62") (name "Net-(IC10A-+IN)") (class "Default")
      (node (ref "C8") (pin "1") (pinfunction "1_1") (pintype "passive"))
      (node (ref "IC10") (pin "3") (pinfunction "+IN_3") (pintype "input"))
      (node (ref "R1") (pin "1") (pinfunction "1_1") (pintype "passive"))
    )
    (net (code "63") (name "Net-(IC10A--IN)") (class "Default")
      (node (ref "IC10") (pin "2") (pinfunction "-IN_2") (pintype "input"))
      (node (ref "R2") (pin "2") (pinfunction "2_2") (pintype "passive"))
    )
    (net (code "64") (name "Net-(IC10A-OUT)") (class "Default")
      (node (ref "IC10") (pin "1") (pinfunction "OUT_1") (pintype "output"))
      (node (ref "R42") (pin "2") (pinfunction "2_2") (pintype "passive"))
    )
    (net (code "65") (name "Net-(IC10B-+IN)") (class "Default")
      (node (ref "IC10") (pin "5") (pinfunction "+IN_5") (pintype "input"))
      (node (ref "R43") (pin "2") (pinfunction "2_2") (pintype "passive"))
      (node (ref "R44") (pin "2") (pinfunction "2_2") (pintype "passive"))
    )
    (net (code "66") (name "Net-(IC10B--IN)") (class "Default")
      (node (ref "IC10") (pin "6") (pinfunction "-IN_6") (pintype "input"))
      (node (ref "R45") (pin "1") (pinfunction "1_1") (pintype "passive"))
      (node (ref "R46") (pin "2") (pinfunction "2_2") (pintype "passive"))
    )
    (net (code "67") (name "Net-(IC10B-OUT)") (class "Default")
      (node (ref "IC10") (pin "7") (pinfunction "OUT_7") (pintype "output"))
      (node (ref "R32") (pin "1") (pinfunction "1_1") (pintype "passive"))
      (node (ref "R44") (pin "1") (pinfunction "1_1") (pintype "passive"))
    )
    (net (code "68") (name "Net-(JP1-Pad2)") (class "Default")
      (node (ref "JP1") (pin "2") (pinfunction "2_2") (pintype "passive"))
      (node (ref "R36") (pin "2") (pinfunction "2_2") (pintype "passive"))
      (node (ref "R37") (pin "2") (pinfunction "2_2") (pintype "passive"))
      (node (ref "SJ1") (pin "2") (pinfunction "2_2") (pintype "passive"))
    )
    (net (code "69") (name "Net-(JP3-Pad1)") (class "Default")
      (node (ref "JP3") (pin "1") (pinfunction "1_1") (pintype "passive"))
      (node (ref "R23") (pin "2") (pinfunction "2_2") (pintype "passive"))
    )
    (net (code "70") (name "Net-(LED1-PadA)") (class "Default")
      (node (ref "LED1") (pin "A") (pinfunction "A_A") (pintype "passive"))
      (node (ref "LED2") (pin "A") (pinfunction "A_A") (pintype "passive"))
      (node (ref "LED3") (pin "A") (pinfunction "A_A") (pintype "passive"))
      (node (ref "LED4") (pin "A") (pinfunction "A_A") (pintype "passive"))
      (node (ref "LED7") (pin "A") (pinfunction "A_A") (pintype "passive"))
      (node (ref "R11") (pin "1") (pinfunction "1_1") (pintype "passive"))
    )
    (net (code "71") (name "Net-(LED6-C)") (class "Default")
      (node (ref "LED6") (pin "K") (pinfunction "C_K") (pintype "passive"))
      (node (ref "R4") (pin "1") (pinfunction "1_1") (pintype "passive"))
    )
    (net (code "72") (name "Net-(Q1-B)") (class "Default")
      (node (ref "Q1") (pin "1") (pinfunction "B_1") (pintype "passive"))
      (node (ref "Q3") (pin "1") (pinfunction "B_1") (pintype "passive"))
      (node (ref "R13") (pin "2") (pinfunction "2_2") (pintype "passive"))
    )
    (net (code "73") (name "Net-(Q2-B)") (class "Default")
      (node (ref "Q2") (pin "1") (pinfunction "B_1") (pintype "passive"))
      (node (ref "Q4") (pin "1") (pinfunction "B_1") (pintype "passive"))
      (node (ref "R9") (pin "1") (pinfunction "1_1") (pintype "passive"))
    )
    (net (code "74") (name "Net-(Q5-B)") (class "Default")
      (node (ref "Q5") (pin "1") (pinfunction "B_1") (pintype "passive"))
      (node (ref "Q6") (pin "1") (pinfunction "B_1") (pintype "passive"))
      (node (ref "Q6") (pin "2") (pinfunction "C_2") (pintype "passive"))
      (node (ref "Q7") (pin "1") (pinfunction "B_1") (pintype "passive"))
      (node (ref "Q7") (pin "2") (pinfunction "C_2") (pintype "passive"))
      (node (ref "Q8") (pin "1") (pinfunction "B_1") (pintype "passive"))
      (node (ref "R38") (pin "1") (pinfunction "1_1") (pintype "passive"))
      (node (ref "R39") (pin "1") (pinfunction "1_1") (pintype "passive"))
      (node (ref "T1") (pin "2") (pinfunction "B_2") (pintype "passive"))
      (node (ref "T1") (pin "4") (pinfunction "B_4") (pintype "passive"))
      (node (ref "T1") (pin "6") (pinfunction "C1_6") (pintype "passive"))
      (node (ref "X2") (pin "2") (pinfunction "S_2") (pintype "passive"))
    )
    (net (code "75") (name "Net-(Q5-E)") (class "Default")
      (node (ref "Q5") (pin "3") (pinfunction "E_3") (pintype "passive"))
      (node (ref "Q8") (pin "3") (pinfunction "E_3") (pintype "passive"))
      (node (ref "R21") (pin "2") (pinfunction "2_2") (pintype "passive"))
      (node (ref "T1") (pin "1") (pinfunction "E_1") (pintype "passive"))
    )
    (net (code "76") (name "Net-(Q6-E)") (class "Default")
      (node (ref "Q6") (pin "3") (pinfunction "E_3") (pintype "passive"))
      (node (ref "Q7") (pin "3") (pinfunction "E_3") (pintype "passive"))
      (node (ref "R20") (pin "2") (pinfunction "2_2") (pintype "passive"))
      (node (ref "T1") (pin "3") (pinfunction "E_3") (pintype "passive"))
    )
    (net (code "77") (name "Net-(Q9-B)") (class "Default")
      (node (ref "Q9") (pin "1") (pinfunction "B_1") (pintype "passive"))
      (node (ref "R32") (pin "2") (pinfunction "2_2") (pintype "passive"))
      (node (ref "T3") (pin "B") (pinfunction "B_B") (pintype "passive"))
    )
    (net (code "78") (name "Net-(Q10-D)") (class "Default")
      (node (ref "Q10") (pin "3") (pinfunction "D_3") (pintype "passive"))
      (node (ref "R7") (pin "2") (pinfunction "2_2") (pintype "passive"))
    )
    (net (code "79") (name "Net-(R14-Pad1)") (class "Default")
      (node (ref "R14") (pin "1") (pinfunction "1_1") (pintype "passive"))
      (node (ref "R7") (pin "1") (pinfunction "1_1") (pintype "passive"))
      (node (ref "U$2") (pin "3") (pinfunction "3_3") (pintype "passive"))
    )
    (net (code "80") (name "Net-(R27-Pad2)") (class "Default")
      (node (ref "R27") (pin "2") (pinfunction "2_2") (pintype "passive"))
      (node (ref "R28") (pin "1") (pinfunction "1_1") (pintype "passive"))
    )
    (net (code "81") (name "Net-(R33-Pad2)") (class "Default")
      (node (ref "R33") (pin "2") (pinfunction "2_2") (pintype "passive"))
      (node (ref "X1") (pin "16") (pinfunction "16_16") (pintype "passive"))
    )
    (net (code "82") (name "VCC") (class "Default")
      (node (ref "6V") (pin "TP") (pinfunction "PP_TP") (pintype "input"))
      (node (ref "C4") (pin "1") (pinfunction "1_1") (pintype "passive"))
      (node (ref "IC1") (pin "OUT") (pinfunction "OUT_OUT") (pintype "passive"))
      (node (ref "IC10") (pin "8") (pinfunction "V+_8") (pintype "power_in"))
      (node (ref "IC2") (pin "1") (pinfunction "OUT_1") (pintype "passive"))
      (node (ref "IC7") (pin "3") (pinfunction "V+_3") (pintype "power_in"))
      (node (ref "R11") (pin "2") (pinfunction "2_2") (pintype "passive"))
      (node (ref "R15") (pin "2") (pinfunction "2_2") (pintype "passive"))
      (node (ref "R19") (pin "1") (pinfunction "1_1") (pintype "passive"))
      (node (ref "R45") (pin "2") (pinfunction "2_2") (pintype "passive"))
      (node (ref "R6") (pin "2") (pinfunction "2_2") (pintype "passive"))
    )
    (net (code "83") (name "unconnected-(IC3A-Q6-Pad7)") (class "Default")
      (node (ref "IC3") (pin "7") (pinfunction "Q6_7") (pintype "output"))
    )
    (net (code "84") (name "unconnected-(IC3A-Q7-Pad4)") (class "Default")
      (node (ref "IC3") (pin "4") (pinfunction "Q7_4") (pintype "output"))
    )
    (net (code "85") (name "unconnected-(IC3A-Q8-Pad9)") (class "Default")
      (node (ref "IC3") (pin "9") (pinfunction "Q8_9") (pintype "output"))
    )
    (net (code "86") (name "unconnected-(IC3A-Q9-Pad5)") (class "Default")
      (node (ref "IC3") (pin "5") (pinfunction "Q9_5") (pintype "output"))
    )
    (net (code "87") (name "unconnected-(IC5-DIS-Pad7)") (class "Default")
      (node (ref "IC5") (pin "7") (pinfunction "DIS_7") (pintype "input"))
    )
    (net (code "88") (name "unconnected-(IC7D-OUT-Pad13)") (class "Default")
      (node (ref "IC7") (pin "13") (pinfunction "OUT_13") (pintype "open_collector"))
    )
    (net (code "89") (name "unconnected-(IC8A-Q-Pad6)") (class "Default")
      (node (ref "IC8") (pin "6") (pinfunction "Q_6") (pintype "output"))
    )
    (net (code "90") (name "unconnected-(IC8A-T2-Pad2)") (class "Default")
      (node (ref "IC8") (pin "2") (pinfunction "T2_2") (pintype "input"))
    )
    (net (code "91") (name "unconnected-(IC8A-~{Q}-Pad7)") (class "Default")
      (node (ref "IC8") (pin "7") (pinfunction "~{Q}_7") (pintype "output"))
    )
    (net (code "92") (name "unconnected-(IC8B-Q-Pad10)") (class "Default")
      (node (ref "IC8") (pin "10") (pinfunction "Q_10") (pintype "output"))
    )
    (net (code "93") (name "unconnected-(Q3-C{slash}-Pad4)") (class "Default")
      (node (ref "Q3") (pin "4") (pinfunction "C/_4") (pintype "passive"))
    )
    (net (code "94") (name "unconnected-(Q4-C{slash}-Pad4)") (class "Default")
      (node (ref "Q4") (pin "4") (pinfunction "C/_4") (pintype "passive"))
    )
    (net (code "95") (name "unconnected-(Q5-C{slash}-Pad4)") (class "Default")
      (node (ref "Q5") (pin "4") (pinfunction "C/_4") (pintype "passive"))
    )
    (net (code "96") (name "unconnected-(Q6-C{slash}-Pad4)") (class "Default")
      (node (ref "Q6") (pin "4") (pinfunction "C/_4") (pintype "passive"))
    )
    (net (code "97") (name "unconnected-(T1A-C-Pad5)") (class "Default")
      (node (ref "T1") (pin "5") (pinfunction "C_5") (pintype "passive"))
    )
    (net (code "98") (name "unconnected-(T1B-C-Pad7)") (class "Default")
      (node (ref "T1") (pin "7") (pinfunction "C_7") (pintype "passive"))
    )
    (net (code "99") (name "unconnected-(X1-Pad20)") (class "Default")
      (node (ref "X1") (pin "20") (pinfunction "20_20") (pintype "passive"))
    )
    (net (code "100") (name "unconnected-(X1-Pad24)") (class "Default")
      (node (ref "X1") (pin "24") (pinfunction "24_24") (pintype "passive"))
    )
  )
)
